# Handle.net
KiCad netlist of a schematic drawn in Altium Designer
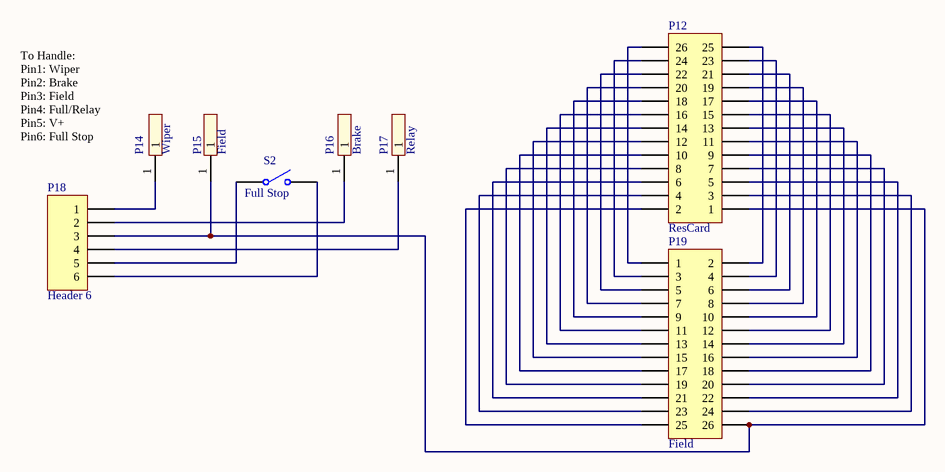
[diagram p0: Handle.SchDoc]

(export (version "E")
  (design (tool "Eeschema 10.0.6"))
  (components
    (comp (ref "P12")
      (value "ResCard")
      (footprint "HDR2X13")
      (description "Header, 13-Pin, Dual row")
      (fields (field (name "PUBLISHER") "Altium Limited"))
      (libsource (lib "Miscellaneous Connectors") (part "Header 13X2"))
    )
    (comp (ref "P14") (value "Wiper") (footprint "1Pin") (libsource (lib "Schlib1") (part "Component_1")))
    (comp (ref "P15") (value "Field") (footprint "1Pin") (libsource (lib "SpecificComponents") (part "1Pin")))
    (comp (ref "P16") (value "Brake") (footprint "1Pin") (libsource (lib "Schlib1") (part "Component_1")))
    (comp (ref "P17") (value "Relay") (footprint "1Pin") (libsource (lib "Schlib1") (part "Component_1")))
    (comp (ref "P18")
      (value "Header 6")
      (footprint "Interconnect")
      (description "Header, 6-Pin")
      (fields (field (name "PUBLISHER") "Altium Limited"))
      (libsource (lib "Miscellaneous Connectors") (part "Header 6"))
    )
    (comp (ref "P19")
      (value "Field")
      (footprint "Wiper Field")
      (description "Header, 13-Pin, Dual row")
      (fields (field (name "PUBLISHER") "Altium Limited"))
      (libsource (lib "") (part "Header 13X2_1"))
    )
    (comp (ref "S2")
      (value "Full Stop")
      (footprint "HDR1X2")
      (description "Single-Pole, Single-Throw Switch")
      (fields (field (name "PUBLISHER") "Altium Limited"))
      (libsource (lib "Miscellaneous Devices") (part "SW-SPST"))
    )
  )
  (nets
    (net (code "1") (name "Net-(P12-Pad1)") (class "Default")
      (node (ref "P12") (pin "1") (pinfunction "1_1") (pintype "passive"))
      (node (ref "P15") (pin "1") (pinfunction "1_1") (pintype "passive"))
      (node (ref "P18") (pin "3") (pinfunction "3_3") (pintype "passive"))
      (node (ref "P19") (pin "26") (pinfunction "26_26") (pintype "passive"))
    )
    (net (code "2") (name "Net-(P12-Pad2)") (class "Default")
      (node (ref "P12") (pin "2") (pinfunction "2_2") (pintype "passive"))
      (node (ref "P19") (pin "25") (pinfunction "25_25") (pintype "passive"))
    )
    (net (code "3") (name "Net-(P12-Pad3)") (class "Default")
      (node (ref "P12") (pin "3") (pinfunction "3_3") (pintype "passive"))
      (node (ref "P19") (pin "24") (pinfunction "24_24") (pintype "passive"))
    )
    (net (code "4") (name "Net-(P12-Pad4)") (class "Default")
      (node (ref "P12") (pin "4") (pinfunction "4_4") (pintype "passive"))
      (node (ref "P19") (pin "23") (pinfunction "23_23") (pintype "passive"))
    )
    (net (code "5") (name "Net-(P12-Pad5)") (class "Default")
      (node (ref "P12") (pin "5") (pinfunction "5_5") (pintype "passive"))
      (node (ref "P19") (pin "22") (pinfunction "22_22") (pintype "passive"))
    )
    (net (code "6") (name "Net-(P12-Pad6)") (class "Default")
      (node (ref "P12") (pin "6") (pinfunction "6_6") (pintype "passive"))
      (node (ref "P19") (pin "21") (pinfunction "21_21") (pintype "passive"))
    )
    (net (code "7") (name "Net-(P12-Pad7)") (class "Default")
      (node (ref "P12") (pin "7") (pinfunction "7_7") (pintype "passive"))
      (node (ref "P19") (pin "20") (pinfunction "20_20") (pintype "passive"))
    )
    (net (code "8") (name "Net-(P12-Pad8)") (class "Default")
      (node (ref "P12") (pin "8") (pinfunction "8_8") (pintype "passive"))
      (node (ref "P19") (pin "19") (pinfunction "19_19") (pintype "passive"))
    )
    (net (code "9") (name "Net-(P12-Pad9)") (class "Default")
      (node (ref "P12") (pin "9") (pinfunction "9_9") (pintype "passive"))
      (node (ref "P19") (pin "18") (pinfunction "18_18") (pintype "passive"))
    )
    (net (code "10") (name "Net-(P12-Pad10)") (class "Default")
      (node (ref "P12") (pin "10") (pinfunction "10_10") (pintype "passive"))
      (node (ref "P19") (pin "17") (pinfunction "17_17") (pintype "passive"))
    )
    (net (code "11") (name "Net-(P12-Pad11)") (class "Default")
      (node (ref "P12") (pin "11") (pinfunction "11_11") (pintype "passive"))
      (node (ref "P19") (pin "16") (pinfunction "16_16") (pintype "passive"))
    )
    (net (code "12") (name "Net-(P12-Pad12)") (class "Default")
      (node (ref "P12") (pin "12") (pinfunction "12_12") (pintype "passive"))
      (node (ref "P19") (pin "15") (pinfunction "15_15") (pintype "passive"))
    )
    (net (code "13") (name "Net-(P12-Pad13)") (class "Default")
      (node (ref "P12") (pin "13") (pinfunction "13_13") (pintype "passive"))
      (node (ref "P19") (pin "14") (pinfunction "14_14") (pintype "passive"))
    )
    (net (code "14") (name "Net-(P12-Pad14)") (class "Default")
      (node (ref "P12") (pin "14") (pinfunction "14_14") (pintype "passive"))
      (node (ref "P19") (pin "13") (pinfunction "13_13") (pintype "passive"))
    )
    (net (code "15") (name "Net-(P12-Pad15)") (class "Default")
      (node (ref "P12") (pin "15") (pinfunction "15_15") (pintype "passive"))
      (node (ref "P19") (pin "12") (pinfunction "12_12") (pintype "passive"))
    )
    (net (code "16") (name "Net-(P12-Pad16)") (class "Default")
      (node (ref "P12") (pin "16") (pinfunction "16_16") (pintype "passive"))
      (node (ref "P19") (pin "11") (pinfunction "11_11") (pintype "passive"))
    )
    (net (code "17") (name "Net-(P12-Pad17)") (class "Default")
      (node (ref "P12") (pin "17") (pinfunction "17_17") (pintype "passive"))
      (node (ref "P19") (pin "10") (pinfunction "10_10") (pintype "passive"))
    )
    (net (code "18") (name "Net-(P12-Pad18)") (class "Default")
      (node (ref "P12") (pin "18") (pinfunction "18_18") (pintype "passive"))
      (node (ref "P19") (pin "9") (pinfunction "9_9") (pintype "passive"))
    )
    (net (code "19") (name "Net-(P12-Pad19)") (class "Default")
      (node (ref "P12") (pin "19") (pinfunction "19_19") (pintype "passive"))
      (node (ref "P19") (pin "8") (pinfunction "8_8") (pintype "passive"))
    )
    (net (code "20") (name "Net-(P12-Pad20)") (class "Default")
      (node (ref "P12") (pin "20") (pinfunction "20_20") (pintype "passive"))
      (node (ref "P19") (pin "7") (pinfunction "7_7") (pintype "passive"))
    )
    (net (code "21") (name "Net-(P12-Pad21)") (class "Default")
      (node (ref "P12") (pin "21") (pinfunction "21_21") (pintype "passive"))
      (node (ref "P19") (pin "6") (pinfunction "6_6") (pintype "passive"))
    )
    (net (code "22") (name "Net-(P12-Pad22)") (class "Default")
      (node (ref "P12") (pin "22") (pinfunction "22_22") (pintype "passive"))
      (node (ref "P19") (pin "5") (pinfunction "5_5") (pintype "passive"))
    )
    (net (code "23") (name "Net-(P12-Pad23)") (class "Default")
      (node (ref "P12") (pin "23") (pinfunction "23_23") (pintype "passive"))
      (node (ref "P19") (pin "4") (pinfunction "4_4") (pintype "passive"))
    )
    (net (code "24") (name "Net-(P12-Pad24)") (class "Default")
      (node (ref "P12") (pin "24") (pinfunction "24_24") (pintype "passive"))
      (node (ref "P19") (pin "3") (pinfunction "3_3") (pintype "passive"))
    )
    (net (code "25") (name "Net-(P12-Pad25)") (class "Default")
      (node (ref "P12") (pin "25") (pinfunction "25_25") (pintype "passive"))
      (node (ref "P19") (pin "2") (pinfunction "2_2") (pintype "passive"))
    )
    (net (code "26") (name "Net-(P12-Pad26)") (class "Default")
      (node (ref "P12") (pin "26") (pinfunction "26_26") (pintype "passive"))
      (node (ref "P19") (pin "1") (pinfunction "1_1") (pintype "passive"))
    )
    (net (code "27") (name "Net-(P14-Pad1)") (class "Default")
      (node (ref "P14") (pin "1") (pinfunction "1_1") (pintype "passive"))
      (node (ref "P18") (pin "1") (pinfunction "1_1") (pintype "passive"))
    )
    (net (code "28") (name "Net-(P16-Pad1)") (class "Default")
      (node (ref "P16") (pin "1") (pinfunction "1_1") (pintype "passive"))
      (node (ref "P18") (pin "2") (pinfunction "2_2") (pintype "passive"))
    )
    (net (code "29") (name "Net-(P17-Pad1)") (class "Default")
      (node (ref "P17") (pin "1") (pinfunction "1_1") (pintype "passive"))
      (node (ref "P18") (pin "4") (pinfunction "4_4") (pintype "passive"))
    )
    (net (code "30") (name "Net-(S2-COMMON)") (class "Default")
      (node (ref "P18") (pin "5") (pinfunction "5_5") (pintype "passive"))
      (node (ref "S2") (pin "1") (pinfunction "COMMON_1") (pintype "passive"))
    )
    (net (code "31") (name "Net-(S2-NO)") (class "Default")
      (node (ref "P18") (pin "6") (pinfunction "6_6") (pintype "passive"))
      (node (ref "S2") (pin "2") (pinfunction "NO_2") (pintype "passive"))
    )
  )
)
